# aircopter-v3.net
KiCad netlist of a schematic drawn in EAGLE
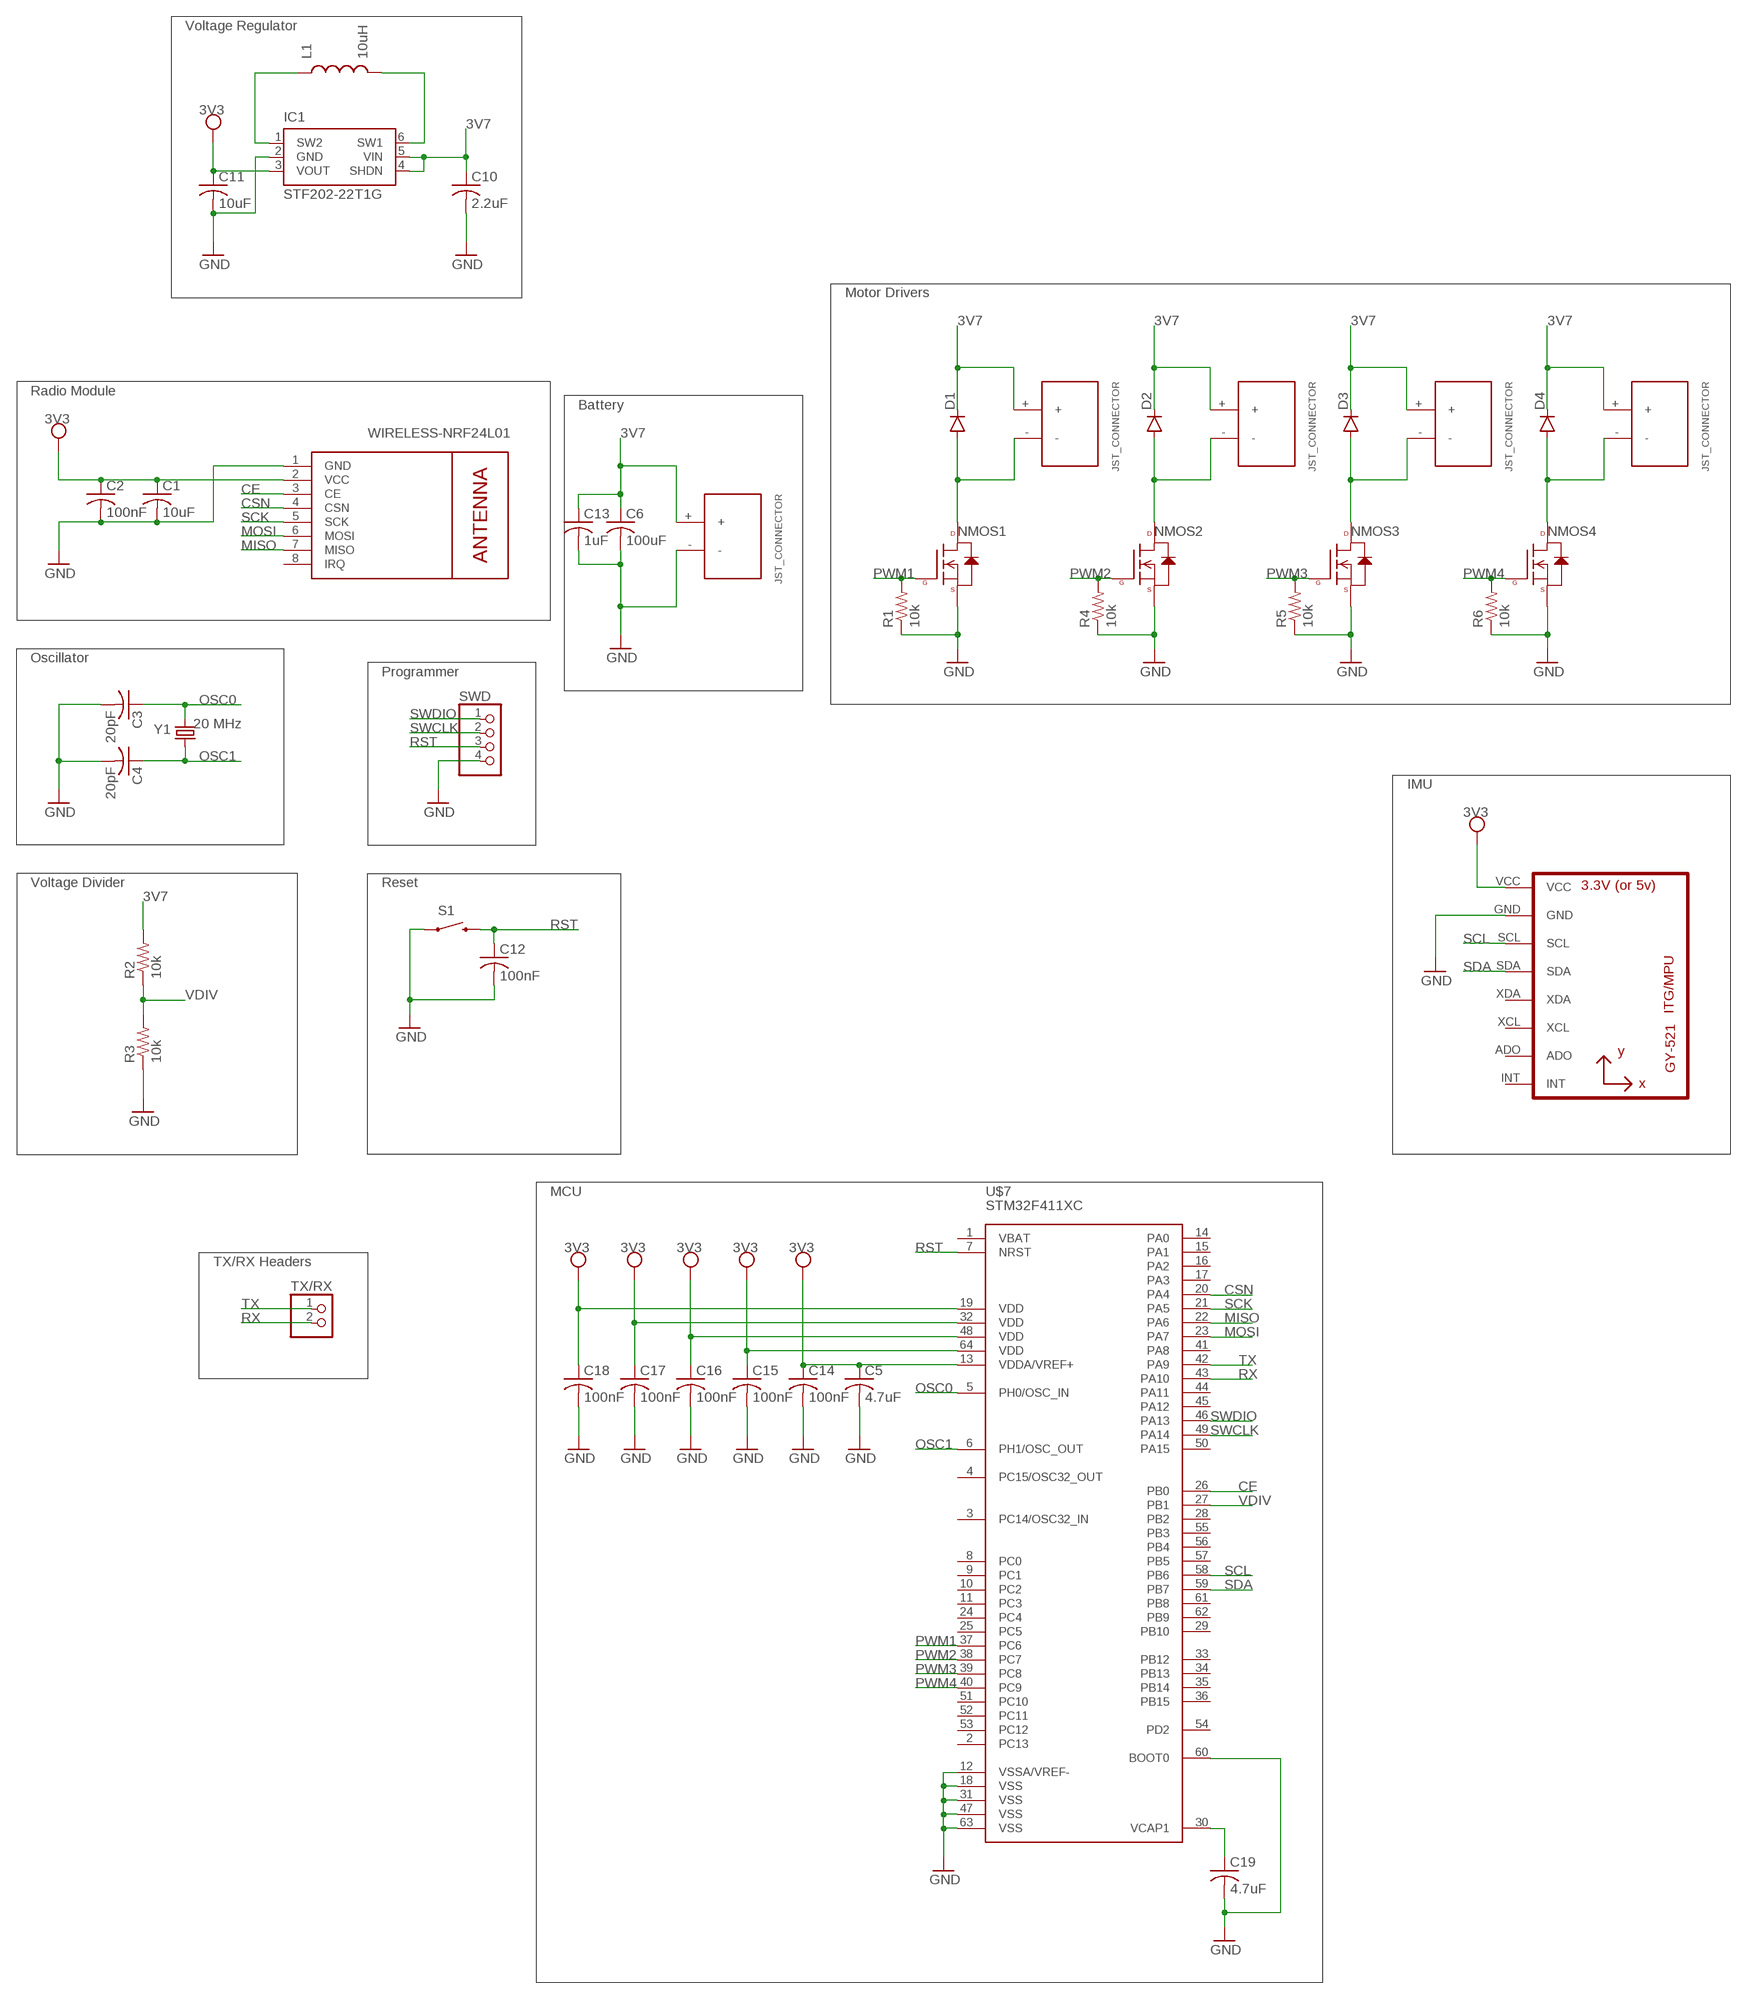
[diagram p0: schematic, sheet 1]

(export (version "E")
  (design (tool "Eeschema 10.0.6"))
  (components
    (comp (ref "C1")
      (value "10uF")
      (footprint "eagle-import:C0603")
      (libsource (lib "eagle-import") (part "C-USC0603"))
    )
    (comp (ref "C2")
      (value "100nF")
      (footprint "eagle-import:C0603")
      (libsource (lib "eagle-import") (part "C-USC0603"))
    )
    (comp (ref "C3")
      (value "20pF")
      (footprint "eagle-import:C0603")
      (libsource (lib "eagle-import") (part "C-USC0603"))
    )
    (comp (ref "C4")
      (value "20pF")
      (footprint "eagle-import:C0603")
      (libsource (lib "eagle-import") (part "C-USC0603"))
    )
    (comp (ref "C5")
      (value "4.7uF")
      (footprint "eagle-import:C0603")
      (libsource (lib "eagle-import") (part "C-USC0603"))
    )
    (comp (ref "C6")
      (value "100uF")
      (footprint "eagle-import:C1206")
      (libsource (lib "eagle-import") (part "C-USC1206"))
    )
    (comp (ref "C10")
      (value "2.2uF")
      (footprint "eagle-import:C0603")
      (libsource (lib "eagle-import") (part "C-USC0603"))
    )
    (comp (ref "C11")
      (value "10uF")
      (footprint "eagle-import:C0603")
      (libsource (lib "eagle-import") (part "C-USC0603"))
    )
    (comp (ref "C12")
      (value "100nF")
      (footprint "eagle-import:C0603")
      (libsource (lib "eagle-import") (part "C-USC0603"))
    )
    (comp (ref "C13")
      (value "1uF")
      (footprint "eagle-import:C0603")
      (libsource (lib "eagle-import") (part "C-USC0603"))
    )
    (comp (ref "C14")
      (value "100nF")
      (footprint "eagle-import:C0603")
      (libsource (lib "eagle-import") (part "C-USC0603"))
    )
    (comp (ref "C15")
      (value "100nF")
      (footprint "eagle-import:C0603")
      (libsource (lib "eagle-import") (part "C-USC0603"))
    )
    (comp (ref "C16")
      (value "100nF")
      (footprint "eagle-import:C0603")
      (libsource (lib "eagle-import") (part "C-USC0603"))
    )
    (comp (ref "C17")
      (value "100nF")
      (footprint "eagle-import:C0603")
      (libsource (lib "eagle-import") (part "C-USC0603"))
    )
    (comp (ref "C18")
      (value "100nF")
      (footprint "eagle-import:C0603")
      (libsource (lib "eagle-import") (part "C-USC0603"))
    )
    (comp (ref "C19")
      (value "4.7uF")
      (footprint "eagle-import:C0603")
      (libsource (lib "eagle-import") (part "C-USC0603"))
    )
    (comp (ref "D1")
      (value "DIODESMA")
      (footprint "eagle-import:SMA-DIODE")
      (libsource (lib "eagle-import") (part "DIODESMA"))
    )
    (comp (ref "D2")
      (value "DIODESMA")
      (footprint "eagle-import:SMA-DIODE")
      (libsource (lib "eagle-import") (part "DIODESMA"))
    )
    (comp (ref "D3")
      (value "DIODESMA")
      (footprint "eagle-import:SMA-DIODE")
      (libsource (lib "eagle-import") (part "DIODESMA"))
    )
    (comp (ref "D4")
      (value "DIODESMA")
      (footprint "eagle-import:SMA-DIODE")
      (libsource (lib "eagle-import") (part "DIODESMA"))
    )
    (comp (ref "IC1")
      (value "STF202-22T1G")
      (footprint "eagle-import:SOT23-6")
      (fields (field (name "MF") "ON Semiconductor"))
      (libsource (lib "eagle-import") (part "STF202-22T1G"))
    )
    (comp (ref "L1")
      (value "10uH")
      (footprint "eagle-import:L0603")
      (libsource (lib "eagle-import") (part "INDUCTOR"))
    )
    (comp (ref "M1")
      (value "WIRELESS-NRF24L01")
      (footprint "eagle-import:WIRELESS-NRF24L01")
      (libsource (lib "eagle-import") (part "WIRELESS-NRF24L01"))
    )
    (comp (ref "NMOS1")
      (value "N-CHANNEL-MOSFET-BSS138")
      (footprint "eagle-import:SOT23-3")
      (libsource (lib "eagle-import") (part "N-CHANNEL-MOSFET-BSS138"))
    )
    (comp (ref "NMOS2")
      (value "N-CHANNEL-MOSFET-BSS138")
      (footprint "eagle-import:SOT23-3")
      (libsource (lib "eagle-import") (part "N-CHANNEL-MOSFET-BSS138"))
    )
    (comp (ref "NMOS3")
      (value "N-CHANNEL-MOSFET-BSS138")
      (footprint "eagle-import:SOT23-3")
      (libsource (lib "eagle-import") (part "N-CHANNEL-MOSFET-BSS138"))
    )
    (comp (ref "NMOS4")
      (value "N-CHANNEL-MOSFET-BSS138")
      (footprint "eagle-import:SOT23-3")
      (libsource (lib "eagle-import") (part "N-CHANNEL-MOSFET-BSS138"))
    )
    (comp (ref "R1")
      (value "10k")
      (footprint "eagle-import:R0603")
      (libsource (lib "eagle-import") (part "R-US_R0603"))
    )
    (comp (ref "R2")
      (value "10k")
      (footprint "eagle-import:R0603")
      (libsource (lib "eagle-import") (part "R-US_R0603"))
    )
    (comp (ref "R3")
      (value "10k")
      (footprint "eagle-import:R0603")
      (libsource (lib "eagle-import") (part "R-US_R0603"))
    )
    (comp (ref "R4")
      (value "10k")
      (footprint "eagle-import:R0603")
      (libsource (lib "eagle-import") (part "R-US_R0603"))
    )
    (comp (ref "R5")
      (value "10k")
      (footprint "eagle-import:R0603")
      (libsource (lib "eagle-import") (part "R-US_R0603"))
    )
    (comp (ref "R6")
      (value "10k")
      (footprint "eagle-import:R0603")
      (libsource (lib "eagle-import") (part "R-US_R0603"))
    )
    (comp (ref "S1")
      (value "SWITCH-MOMENTARY-2SMD")
      (footprint "eagle-import:TACTILE-SWITCH-SMD")
      (libsource (lib "eagle-import") (part "SWITCH-MOMENTARY-2SMD"))
    )
    (comp (ref "SWD")
      (value "PINHD-1X4")
      (footprint "eagle-import:1X04")
      (libsource (lib "eagle-import") (part "PINHD-1X4"))
    )
    (comp (ref "TX/RX")
      (value "PINHD-1X2")
      (footprint "eagle-import:1X02")
      (libsource (lib "eagle-import") (part "PINHD-1X2"))
    )
    (comp (ref "U$2")
      (value "JST_CONNECTOR_FEMALE")
      (footprint "eagle-import:JST_CONNECTOR_FEMALE")
      (libsource (lib "eagle-import") (part "JST_CONNECTOR_FEMALE"))
    )
    (comp (ref "U$3")
      (value "JST_CONNECTOR_FEMALE")
      (footprint "eagle-import:JST_CONNECTOR_FEMALE")
      (libsource (lib "eagle-import") (part "JST_CONNECTOR_FEMALE"))
    )
    (comp (ref "U$4")
      (value "JST_CONNECTOR_FEMALE")
      (footprint "eagle-import:JST_CONNECTOR_FEMALE")
      (libsource (lib "eagle-import") (part "JST_CONNECTOR_FEMALE"))
    )
    (comp (ref "U$5")
      (value "JST_CONNECTOR_FEMALE")
      (footprint "eagle-import:JST_CONNECTOR_FEMALE")
      (libsource (lib "eagle-import") (part "JST_CONNECTOR_FEMALE"))
    )
    (comp (ref "U$6")
      (value "JST_CONNECTOR_FEMALE")
      (footprint "eagle-import:JST_CONNECTOR_FEMALE")
      (libsource (lib "eagle-import") (part "JST_CONNECTOR_FEMALE"))
    )
    (comp (ref "U$7")
      (value "STM32F411XC")
      (footprint "eagle-import:LQFP64")
      (libsource (lib "eagle-import") (part "STM32F411XC"))
    )
    (comp (ref "U2")
      (value "GY-521MPU6050")
      (footprint "eagle-import:GY-521")
      (libsource (lib "eagle-import") (part "GY-521MPU6050"))
    )
    (comp (ref "Y1")
      (value "20 MHz")
      (footprint "eagle-import:HC49UP")
      (libsource (lib "eagle-import") (part "CRYSTALSMD"))
    )
  )
  (nets
    (net (code "1") (name "/3V7") (class "Default")
      (node (ref "C10") (pin "1") (pinfunction "1_1") (pintype "passive"))
      (node (ref "C13") (pin "1") (pinfunction "1_1") (pintype "passive"))
      (node (ref "C6") (pin "1") (pinfunction "1_1") (pintype "passive"))
      (node (ref "D1") (pin "C") (pinfunction "C_C") (pintype "passive"))
      (node (ref "D2") (pin "C") (pinfunction "C_C") (pintype "passive"))
      (node (ref "D3") (pin "C") (pinfunction "C_C") (pintype "passive"))
      (node (ref "D4") (pin "C") (pinfunction "C_C") (pintype "passive"))
      (node (ref "IC1") (pin "4") (pinfunction "SHDN_4") (pintype "passive"))
      (node (ref "IC1") (pin "5") (pinfunction "VIN_5") (pintype "passive"))
      (node (ref "R2") (pin "2") (pinfunction "2_2") (pintype "passive"))
      (node (ref "U$2") (pin "+") (pinfunction "+_+") (pintype "bidirectional"))
      (node (ref "U$3") (pin "+") (pinfunction "+_+") (pintype "bidirectional"))
      (node (ref "U$4") (pin "+") (pinfunction "+_+") (pintype "bidirectional"))
      (node (ref "U$5") (pin "+") (pinfunction "+_+") (pintype "bidirectional"))
      (node (ref "U$6") (pin "+") (pinfunction "+_+") (pintype "bidirectional"))
    )
    (net (code "2") (name "/CE") (class "Default")
      (node (ref "M1") (pin "3") (pinfunction "CE_3") (pintype "bidirectional"))
      (node (ref "U$7") (pin "26") (pinfunction "PB0_26") (pintype "bidirectional"))
    )
    (net (code "3") (name "/CSN") (class "Default")
      (node (ref "M1") (pin "4") (pinfunction "CSN_4") (pintype "bidirectional"))
      (node (ref "U$7") (pin "20") (pinfunction "PA4_20") (pintype "bidirectional"))
    )
    (net (code "4") (name "/MISO") (class "Default")
      (node (ref "M1") (pin "7") (pinfunction "MISO_7") (pintype "bidirectional"))
      (node (ref "U$7") (pin "22") (pinfunction "PA6_22") (pintype "bidirectional"))
    )
    (net (code "5") (name "/MOSI") (class "Default")
      (node (ref "M1") (pin "6") (pinfunction "MOSI_6") (pintype "bidirectional"))
      (node (ref "U$7") (pin "23") (pinfunction "PA7_23") (pintype "bidirectional"))
    )
    (net (code "6") (name "/OSC0") (class "Default")
      (node (ref "C3") (pin "1") (pinfunction "1_1") (pintype "passive"))
      (node (ref "U$7") (pin "5") (pinfunction "PH0/OSC_IN_5") (pintype "bidirectional"))
      (node (ref "Y1") (pin "2") (pinfunction "2_2") (pintype "passive"))
    )
    (net (code "7") (name "/OSC1") (class "Default")
      (node (ref "C4") (pin "1") (pinfunction "1_1") (pintype "passive"))
      (node (ref "U$7") (pin "6") (pinfunction "PH1/OSC_OUT_6") (pintype "bidirectional"))
      (node (ref "Y1") (pin "1") (pinfunction "1_1") (pintype "passive"))
    )
    (net (code "8") (name "/PWM1") (class "Default")
      (node (ref "NMOS1") (pin "1") (pinfunction "G_1") (pintype "passive"))
      (node (ref "R1") (pin "2") (pinfunction "2_2") (pintype "passive"))
      (node (ref "U$7") (pin "37") (pinfunction "PC6_37") (pintype "bidirectional"))
    )
    (net (code "9") (name "/PWM2") (class "Default")
      (node (ref "NMOS2") (pin "1") (pinfunction "G_1") (pintype "passive"))
      (node (ref "R4") (pin "2") (pinfunction "2_2") (pintype "passive"))
      (node (ref "U$7") (pin "38") (pinfunction "PC7_38") (pintype "bidirectional"))
    )
    (net (code "10") (name "/PWM3") (class "Default")
      (node (ref "NMOS3") (pin "1") (pinfunction "G_1") (pintype "passive"))
      (node (ref "R5") (pin "2") (pinfunction "2_2") (pintype "passive"))
      (node (ref "U$7") (pin "39") (pinfunction "PC8_39") (pintype "bidirectional"))
    )
    (net (code "11") (name "/PWM4") (class "Default")
      (node (ref "NMOS4") (pin "1") (pinfunction "G_1") (pintype "passive"))
      (node (ref "R6") (pin "2") (pinfunction "2_2") (pintype "passive"))
      (node (ref "U$7") (pin "40") (pinfunction "PC9_40") (pintype "bidirectional"))
    )
    (net (code "12") (name "/RST") (class "Default")
      (node (ref "C12") (pin "1") (pinfunction "1_1") (pintype "passive"))
      (node (ref "S1") (pin "3") (pinfunction "2_3") (pintype "passive"))
      (node (ref "SWD") (pin "3") (pinfunction "3_3") (pintype "passive"))
      (node (ref "U$7") (pin "7") (pinfunction "NRST_7") (pintype "bidirectional"))
    )
    (net (code "13") (name "/RX") (class "Default")
      (node (ref "TX/RX") (pin "2") (pinfunction "2_2") (pintype "passive"))
      (node (ref "U$7") (pin "43") (pinfunction "PA10_43") (pintype "bidirectional"))
    )
    (net (code "14") (name "/SCK") (class "Default")
      (node (ref "M1") (pin "5") (pinfunction "SCK_5") (pintype "bidirectional"))
      (node (ref "U$7") (pin "21") (pinfunction "PA5_21") (pintype "bidirectional"))
    )
    (net (code "15") (name "/SCL") (class "Default")
      (node (ref "U$7") (pin "58") (pinfunction "PB6_58") (pintype "bidirectional"))
      (node (ref "U2") (pin "SCL") (pinfunction "SCL_SCL") (pintype "bidirectional"))
    )
    (net (code "16") (name "/SDA") (class "Default")
      (node (ref "U$7") (pin "59") (pinfunction "PB7_59") (pintype "bidirectional"))
      (node (ref "U2") (pin "SDA") (pinfunction "SDA_SDA") (pintype "bidirectional"))
    )
    (net (code "17") (name "/SWCLK") (class "Default")
      (node (ref "SWD") (pin "2") (pinfunction "2_2") (pintype "passive"))
      (node (ref "U$7") (pin "49") (pinfunction "PA14_49") (pintype "bidirectional"))
    )
    (net (code "18") (name "/SWDIO") (class "Default")
      (node (ref "SWD") (pin "1") (pinfunction "1_1") (pintype "passive"))
      (node (ref "U$7") (pin "46") (pinfunction "PA13_46") (pintype "bidirectional"))
    )
    (net (code "19") (name "/TX") (class "Default")
      (node (ref "TX/RX") (pin "1") (pinfunction "1_1") (pintype "passive"))
      (node (ref "U$7") (pin "42") (pinfunction "PA9_42") (pintype "bidirectional"))
    )
    (net (code "20") (name "/VDIV") (class "Default")
      (node (ref "R2") (pin "1") (pinfunction "1_1") (pintype "passive"))
      (node (ref "R3") (pin "2") (pinfunction "2_2") (pintype "passive"))
      (node (ref "U$7") (pin "27") (pinfunction "PB1_27") (pintype "bidirectional"))
    )
    (net (code "21") (name "3V3-CIRCLE") (class "Default")
      (node (ref "C1") (pin "1") (pinfunction "1_1") (pintype "passive"))
      (node (ref "C11") (pin "1") (pinfunction "1_1") (pintype "passive"))
      (node (ref "C14") (pin "1") (pinfunction "1_1") (pintype "passive"))
      (node (ref "C15") (pin "1") (pinfunction "1_1") (pintype "passive"))
      (node (ref "C16") (pin "1") (pinfunction "1_1") (pintype "passive"))
      (node (ref "C17") (pin "1") (pinfunction "1_1") (pintype "passive"))
      (node (ref "C18") (pin "1") (pinfunction "1_1") (pintype "passive"))
      (node (ref "C2") (pin "1") (pinfunction "1_1") (pintype "passive"))
      (node (ref "C5") (pin "1") (pinfunction "1_1") (pintype "passive"))
      (node (ref "IC1") (pin "3") (pinfunction "VOUT_3") (pintype "passive"))
      (node (ref "M1") (pin "2") (pinfunction "VCC_2") (pintype "power_in"))
      (node (ref "U$7") (pin "13") (pinfunction "VDDA/VREF+_13") (pintype "bidirectional"))
      (node (ref "U$7") (pin "19") (pinfunction "VDD_19") (pintype "bidirectional"))
      (node (ref "U$7") (pin "32") (pinfunction "VDD_32") (pintype "bidirectional"))
      (node (ref "U$7") (pin "48") (pinfunction "VDD_48") (pintype "bidirectional"))
      (node (ref "U$7") (pin "64") (pinfunction "VDD_64") (pintype "bidirectional"))
      (node (ref "U2") (pin "VCC") (pinfunction "VCC_VCC") (pintype "bidirectional"))
    )
    (net (code "22") (name "Net-(IC1-SW1)") (class "Default")
      (node (ref "IC1") (pin "6") (pinfunction "SW1_6") (pintype "passive"))
      (node (ref "L1") (pin "2") (pinfunction "2_2") (pintype "passive"))
    )
    (net (code "23") (name "Net-(IC1-SW2)") (class "Default")
      (node (ref "IC1") (pin "1") (pinfunction "SW2_1") (pintype "passive"))
      (node (ref "L1") (pin "1") (pinfunction "1_1") (pintype "passive"))
    )
    (net (code "24") (name "Net-(NMOS1-D)") (class "Default")
      (node (ref "D1") (pin "A") (pinfunction "A_A") (pintype "passive"))
      (node (ref "NMOS1") (pin "3") (pinfunction "D_3") (pintype "passive"))
      (node (ref "U$2") (pin "-") (pinfunction "-_-") (pintype "bidirectional"))
    )
    (net (code "25") (name "Net-(NMOS2-D)") (class "Default")
      (node (ref "D2") (pin "A") (pinfunction "A_A") (pintype "passive"))
      (node (ref "NMOS2") (pin "3") (pinfunction "D_3") (pintype "passive"))
      (node (ref "U$3") (pin "-") (pinfunction "-_-") (pintype "bidirectional"))
    )
    (net (code "26") (name "Net-(NMOS3-D)") (class "Default")
      (node (ref "D3") (pin "A") (pinfunction "A_A") (pintype "passive"))
      (node (ref "NMOS3") (pin "3") (pinfunction "D_3") (pintype "passive"))
      (node (ref "U$4") (pin "-") (pinfunction "-_-") (pintype "bidirectional"))
    )
    (net (code "27") (name "Net-(NMOS4-D)") (class "Default")
      (node (ref "D4") (pin "A") (pinfunction "A_A") (pintype "passive"))
      (node (ref "NMOS4") (pin "3") (pinfunction "D_3") (pintype "passive"))
      (node (ref "U$5") (pin "-") (pinfunction "-_-") (pintype "bidirectional"))
    )
    (net (code "28") (name "Net-(U$7-VCAP1)") (class "Default")
      (node (ref "C19") (pin "1") (pinfunction "1_1") (pintype "passive"))
      (node (ref "U$7") (pin "30") (pinfunction "VCAP1_30") (pintype "bidirectional"))
    )
    (net (code "29") (name "SUPPLY1_GND") (class "Default")
      (node (ref "C1") (pin "2") (pinfunction "2_2") (pintype "passive"))
      (node (ref "C10") (pin "2") (pinfunction "2_2") (pintype "passive"))
      (node (ref "C11") (pin "2") (pinfunction "2_2") (pintype "passive"))
      (node (ref "C12") (pin "2") (pinfunction "2_2") (pintype "passive"))
      (node (ref "C13") (pin "2") (pinfunction "2_2") (pintype "passive"))
      (node (ref "C14") (pin "2") (pinfunction "2_2") (pintype "passive"))
      (node (ref "C15") (pin "2") (pinfunction "2_2") (pintype "passive"))
      (node (ref "C16") (pin "2") (pinfunction "2_2") (pintype "passive"))
      (node (ref "C17") (pin "2") (pinfunction "2_2") (pintype "passive"))
      (node (ref "C18") (pin "2") (pinfunction "2_2") (pintype "passive"))
      (node (ref "C19") (pin "2") (pinfunction "2_2") (pintype "passive"))
      (node (ref "C2") (pin "2") (pinfunction "2_2") (pintype "passive"))
      (node (ref "C3") (pin "2") (pinfunction "2_2") (pintype "passive"))
      (node (ref "C4") (pin "2") (pinfunction "2_2") (pintype "passive"))
      (node (ref "C5") (pin "2") (pinfunction "2_2") (pintype "passive"))
      (node (ref "C6") (pin "2") (pinfunction "2_2") (pintype "passive"))
      (node (ref "IC1") (pin "2") (pinfunction "GND_2") (pintype "passive"))
      (node (ref "M1") (pin "1") (pinfunction "GND_1") (pintype "power_in"))
      (node (ref "NMOS1") (pin "2") (pinfunction "S_2") (pintype "passive"))
      (node (ref "NMOS2") (pin "2") (pinfunction "S_2") (pintype "passive"))
      (node (ref "NMOS3") (pin "2") (pinfunction "S_2") (pintype "passive"))
      (node (ref "NMOS4") (pin "2") (pinfunction "S_2") (pintype "passive"))
      (node (ref "R1") (pin "1") (pinfunction "1_1") (pintype "passive"))
      (node (ref "R3") (pin "1") (pinfunction "1_1") (pintype "passive"))
      (node (ref "R4") (pin "1") (pinfunction "1_1") (pintype "passive"))
      (node (ref "R5") (pin "1") (pinfunction "1_1") (pintype "passive"))
      (node (ref "R6") (pin "1") (pinfunction "1_1") (pintype "passive"))
      (node (ref "S1") (pin "1") (pinfunction "1_1") (pintype "passive"))
      (node (ref "SWD") (pin "4") (pinfunction "4_4") (pintype "passive"))
      (node (ref "U$6") (pin "-") (pinfunction "-_-") (pintype "bidirectional"))
      (node (ref "U$7") (pin "12") (pinfunction "VSSA/VREF-_12") (pintype "bidirectional"))
      (node (ref "U$7") (pin "18") (pinfunction "VSS_18") (pintype "bidirectional"))
      (node (ref "U$7") (pin "31") (pinfunction "VSS_31") (pintype "bidirectional"))
      (node (ref "U$7") (pin "47") (pinfunction "VSS_47") (pintype "bidirectional"))
      (node (ref "U$7") (pin "60") (pinfunction "BOOT0_60") (pintype "bidirectional"))
      (node (ref "U$7") (pin "63") (pinfunction "VSS_63") (pintype "bidirectional"))
      (node (ref "U2") (pin "GND") (pinfunction "GND_GND") (pintype "bidirectional"))
    )
    (net (code "30") (name "unconnected-(M1-IRQ-Pad8)") (class "Default")
      (node (ref "M1") (pin "8") (pinfunction "IRQ_8") (pintype "bidirectional"))
    )
    (net (code "31") (name "unconnected-(U$7-PA0-Pad14)") (class "Default")
      (node (ref "U$7") (pin "14") (pinfunction "PA0_14") (pintype "bidirectional"))
    )
    (net (code "32") (name "unconnected-(U$7-PA1-Pad15)") (class "Default")
      (node (ref "U$7") (pin "15") (pinfunction "PA1_15") (pintype "bidirectional"))
    )
    (net (code "33") (name "unconnected-(U$7-PA2-Pad16)") (class "Default")
      (node (ref "U$7") (pin "16") (pinfunction "PA2_16") (pintype "bidirectional"))
    )
    (net (code "34") (name "unconnected-(U$7-PA3-Pad17)") (class "Default")
      (node (ref "U$7") (pin "17") (pinfunction "PA3_17") (pintype "bidirectional"))
    )
    (net (code "35") (name "unconnected-(U$7-PA8-Pad41)") (class "Default")
      (node (ref "U$7") (pin "41") (pinfunction "PA8_41") (pintype "bidirectional"))
    )
    (net (code "36") (name "unconnected-(U$7-PA11-Pad44)") (class "Default")
      (node (ref "U$7") (pin "44") (pinfunction "PA11_44") (pintype "bidirectional"))
    )
    (net (code "37") (name "unconnected-(U$7-PA12-Pad45)") (class "Default")
      (node (ref "U$7") (pin "45") (pinfunction "PA12_45") (pintype "bidirectional"))
    )
    (net (code "38") (name "unconnected-(U$7-PA15-Pad50)") (class "Default")
      (node (ref "U$7") (pin "50") (pinfunction "PA15_50") (pintype "bidirectional"))
    )
    (net (code "39") (name "unconnected-(U$7-PB2-Pad28)") (class "Default")
      (node (ref "U$7") (pin "28") (pinfunction "PB2_28") (pintype "bidirectional"))
    )
    (net (code "40") (name "unconnected-(U$7-PB3-Pad55)") (class "Default")
      (node (ref "U$7") (pin "55") (pinfunction "PB3_55") (pintype "bidirectional"))
    )
    (net (code "41") (name "unconnected-(U$7-PB4-Pad56)") (class "Default")
      (node (ref "U$7") (pin "56") (pinfunction "PB4_56") (pintype "bidirectional"))
    )
    (net (code "42") (name "unconnected-(U$7-PB5-Pad57)") (class "Default")
      (node (ref "U$7") (pin "57") (pinfunction "PB5_57") (pintype "bidirectional"))
    )
    (net (code "43") (name "unconnected-(U$7-PB8-Pad61)") (class "Default")
      (node (ref "U$7") (pin "61") (pinfunction "PB8_61") (pintype "bidirectional"))
    )
    (net (code "44") (name "unconnected-(U$7-PB9-Pad62)") (class "Default")
      (node (ref "U$7") (pin "62") (pinfunction "PB9_62") (pintype "bidirectional"))
    )
    (net (code "45") (name "unconnected-(U$7-PB10-Pad29)") (class "Default")
      (node (ref "U$7") (pin "29") (pinfunction "PB10_29") (pintype "bidirectional"))
    )
    (net (code "46") (name "unconnected-(U$7-PB12-Pad33)") (class "Default")
      (node (ref "U$7") (pin "33") (pinfunction "PB12_33") (pintype "bidirectional"))
    )
    (net (code "47") (name "unconnected-(U$7-PB13-Pad34)") (class "Default")
      (node (ref "U$7") (pin "34") (pinfunction "PB13_34") (pintype "bidirectional"))
    )
    (net (code "48") (name "unconnected-(U$7-PB14-Pad35)") (class "Default")
      (node (ref "U$7") (pin "35") (pinfunction "PB14_35") (pintype "bidirectional"))
    )
    (net (code "49") (name "unconnected-(U$7-PB15-Pad36)") (class "Default")
      (node (ref "U$7") (pin "36") (pinfunction "PB15_36") (pintype "bidirectional"))
    )
    (net (code "50") (name "unconnected-(U$7-PC0-Pad8)") (class "Default")
      (node (ref "U$7") (pin "8") (pinfunction "PC0_8") (pintype "bidirectional"))
    )
    (net (code "51") (name "unconnected-(U$7-PC1-Pad9)") (class "Default")
      (node (ref "U$7") (pin "9") (pinfunction "PC1_9") (pintype "bidirectional"))
    )
    (net (code "52") (name "unconnected-(U$7-PC2-Pad10)") (class "Default")
      (node (ref "U$7") (pin "10") (pinfunction "PC2_10") (pintype "bidirectional"))
    )
    (net (code "53") (name "unconnected-(U$7-PC3-Pad11)") (class "Default")
      (node (ref "U$7") (pin "11") (pinfunction "PC3_11") (pintype "bidirectional"))
    )
    (net (code "54") (name "unconnected-(U$7-PC4-Pad24)") (class "Default")
      (node (ref "U$7") (pin "24") (pinfunction "PC4_24") (pintype "bidirectional"))
    )
    (net (code "55") (name "unconnected-(U$7-PC5-Pad25)") (class "Default")
      (node (ref "U$7") (pin "25") (pinfunction "PC5_25") (pintype "bidirectional"))
    )
    (net (code "56") (name "unconnected-(U$7-PC10-Pad51)") (class "Default")
      (node (ref "U$7") (pin "51") (pinfunction "PC10_51") (pintype "bidirectional"))
    )
    (net (code "57") (name "unconnected-(U$7-PC11-Pad52)") (class "Default")
      (node (ref "U$7") (pin "52") (pinfunction "PC11_52") (pintype "bidirectional"))
    )
    (net (code "58") (name "unconnected-(U$7-PC12-Pad53)") (class "Default")
      (node (ref "U$7") (pin "53") (pinfunction "PC12_53") (pintype "bidirectional"))
    )
    (net (code "59") (name "unconnected-(U$7-PC13-Pad2)") (class "Default")
      (node (ref "U$7") (pin "2") (pinfunction "PC13_2") (pintype "bidirectional"))
    )
    (net (code "60") (name "unconnected-(U$7-PC14{slash}OSC32_IN-Pad3)") (class "Default")
      (node (ref "U$7") (pin "3") (pinfunction "PC14/OSC32_IN_3") (pintype "bidirectional"))
    )
    (net (code "61") (name "unconnected-(U$7-PC15{slash}OSC32_OUT-Pad4)") (class "Default")
      (node (ref "U$7") (pin "4") (pinfunction "PC15/OSC32_OUT_4") (pintype "bidirectional"))
    )
    (net (code "62") (name "unconnected-(U$7-PD2-Pad54)") (class "Default")
      (node (ref "U$7") (pin "54") (pinfunction "PD2_54") (pintype "bidirectional"))
    )
    (net (code "63") (name "unconnected-(U$7-VBAT-Pad1)") (class "Default")
      (node (ref "U$7") (pin "1") (pinfunction "VBAT_1") (pintype "bidirectional"))
    )
    (net (code "64") (name "unconnected-(U2-PadADO)") (class "Default")
      (node (ref "U2") (pin "ADO") (pinfunction "ADO_ADO") (pintype "bidirectional"))
    )
    (net (code "65") (name "unconnected-(U2-PadINT)") (class "Default")
      (node (ref "U2") (pin "INT") (pinfunction "INT_INT") (pintype "bidirectional"))
    )
    (net (code "66") (name "unconnected-(U2-PadXCL)") (class "Default")
      (node (ref "U2") (pin "XCL") (pinfunction "XCL_XCL") (pintype "bidirectional"))
    )
    (net (code "67") (name "unconnected-(U2-PadXDA)") (class "Default")
      (node (ref "U2") (pin "XDA") (pinfunction "XDA_XDA") (pintype "bidirectional"))
    )
  )
)
